# PX4FMUv2_4_6_10.net
KiCad netlist of a schematic drawn in Altium Designer
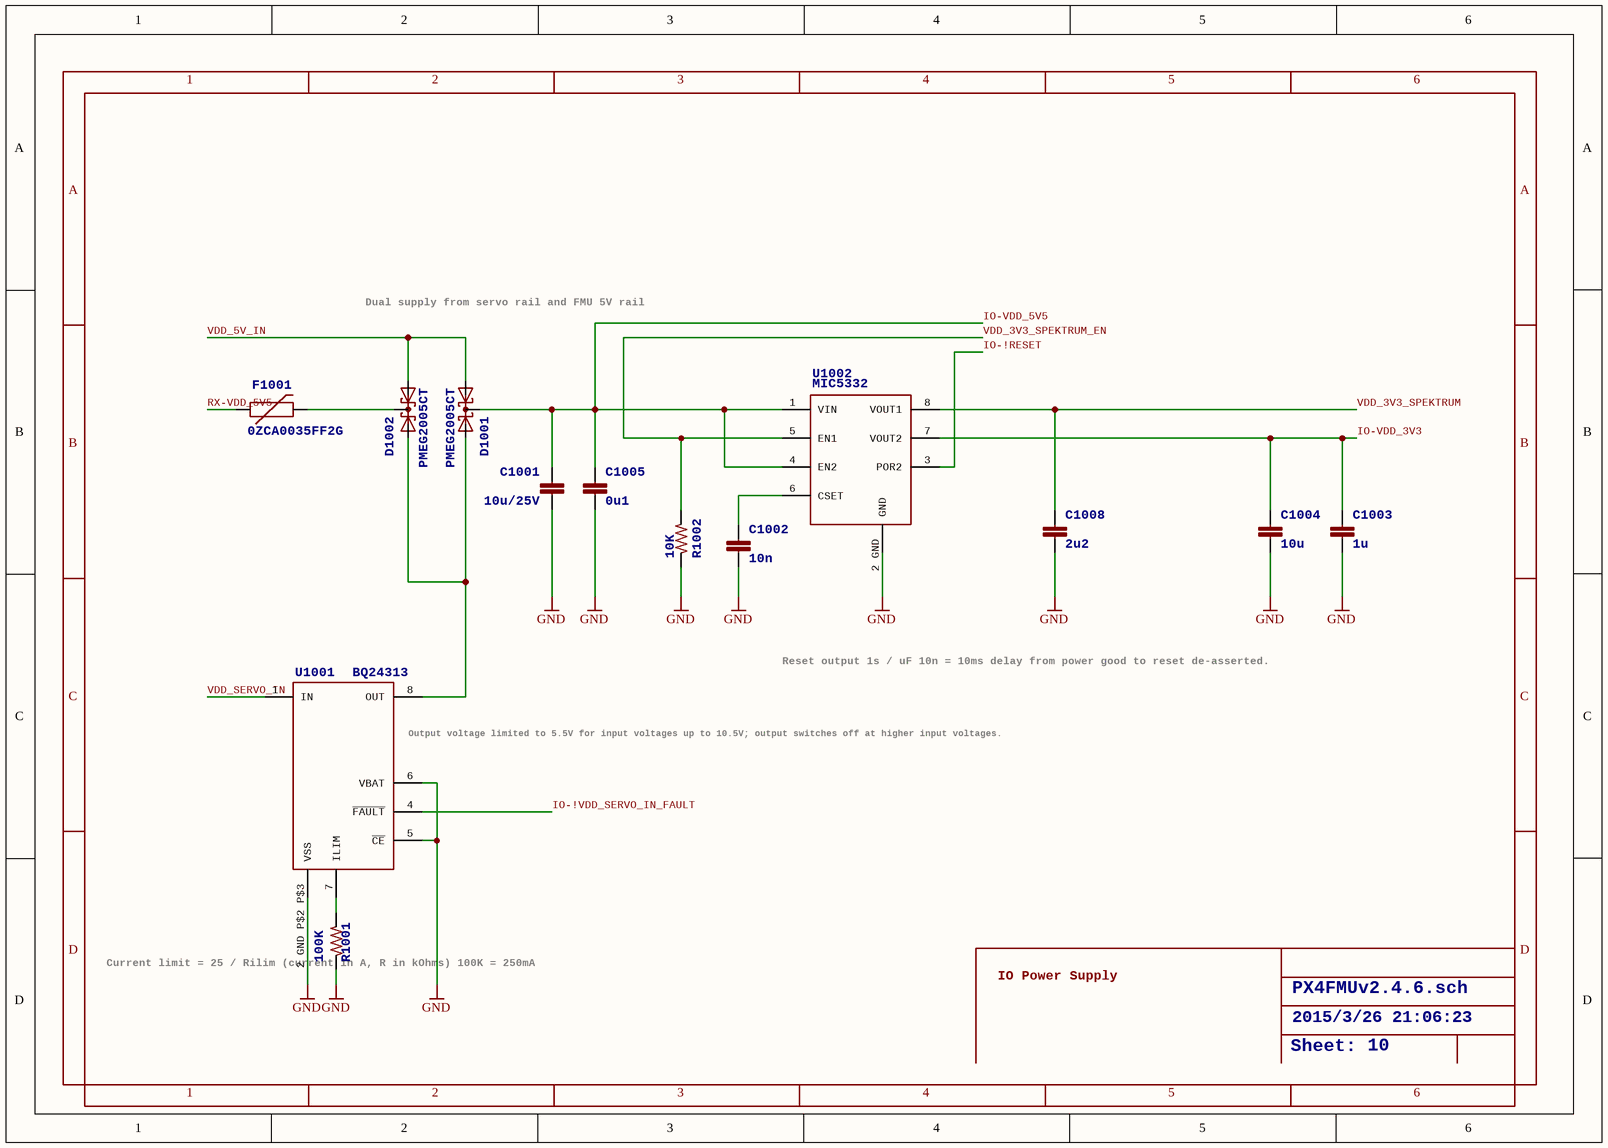
[diagram p0: PX4FMUv2.4.6_10.SchDoc]

(export (version "E")
  (design (tool "Eeschema 10.0.6"))
  (components
    (comp (ref "C1001")
      (value "10u/25V")
      (footprint "0805-CAP")
      (description "<b>Capacitor</b>\nStandard 0603 ceramic capacitor, and 0.1\" leaded capacitor.")
      (fields (field (name "PARTNO") "CL21A106KAYNNNE"))
      (libsource (lib "pixhawk2") (part "CAP0805"))
    )
    (comp (ref "C1002")
      (value "10n")
      (footprint "0402-CAP")
      (description "<b>Capacitor</b>\nStandard 0603 ceramic capacitor, and 0.1\" leaded capacitor.")
      (fields (field (name "PARTNO") "CC0402KRX7R7BB103"))
      (libsource (lib "pixhawk2") (part "CAP0402"))
    )
    (comp (ref "C1003")
      (value "1u")
      (footprint "0603-CAP")
      (description "<b>Capacitor</b>\nStandard 0603 ceramic capacitor, and 0.1\" leaded capacitor.")
      (fields (field (name "PARTNO") "CC0603ZRY5V7BB105"))
      (libsource (lib "pixhawk2") (part "CAP0603"))
    )
    (comp (ref "C1004")
      (value "10u")
      (footprint "0603-CAP")
      (description "<b>Capacitor</b>\nStandard 0603 ceramic capacitor, and 0.1\" leaded capacitor.")
      (fields (field (name "PARTNO") "C1608X5R1A106K080AC"))
      (libsource (lib "pixhawk2") (part "CAP0603"))
    )
    (comp (ref "C1005")
      (value "0u1")
      (footprint "0402-CAP")
      (description "<b>Capacitor</b>\nStandard 0603 ceramic capacitor, and 0.1\" leaded capacitor.")
      (fields (field (name "PARTNO") "CC0402ZRY5V7BB104"))
      (libsource (lib "pixhawk2") (part "CAP0402"))
    )
    (comp (ref "C1008")
      (value "2u2")
      (footprint "0402-CAP")
      (description "<b>Capacitor</b>\nStandard 0603 ceramic capacitor, and 0.1\" leaded capacitor.")
      (fields (field (name "PARTNO") "C1005X6S1C225K050BC"))
      (libsource (lib "pixhawk2") (part "CAP0402"))
    )
    (comp (ref "D1001")
      (value "PMEG2005CT")
      (footprint "SOT23-3")
      (libsource (lib "pixhawk2") (part "PMEG2005CT"))
    )
    (comp (ref "D1002")
      (value "PMEG2005CT")
      (footprint "SOT23-3")
      (libsource (lib "pixhawk2") (part "PMEG2005CT"))
    )
    (comp (ref "F1001")
      (value "0ZCA0035FF2G")
      (footprint "PTC-1206")
      (description "<b>Resettable Fuse PTC</b>\nResettable Fuse. Spark Fun Electronics SKU : COM-08357")
      (libsource (lib "pixhawk2") (part "PTCSMD"))
    )
    (comp (ref "R1001")
      (value "100K")
      (footprint "0402-RES")
      (libsource (lib "pixhawk2") (part "RESISTOR0402-RES"))
    )
    (comp (ref "R1002")
      (value "10K")
      (footprint "0402-RES")
      (fields (field (name "PARTNO") "RC0402FR-0710KL"))
      (libsource (lib "pixhawk2") (part "RESISTOR0402-RES"))
    )
    (comp (ref "U1001")
      (value "BQ24313")
      (footprint "QFN8-DSG")
      (fields (field (name "PARTNO") "BQ24313DSGT"))
      (libsource (lib "pixhawk2") (part "BQ24313"))
    )
    (comp (ref "U1002")
      (value "MIC5332")
      (footprint "MLF-8-EPAD")
      (fields (field (name "PARTNO") "MIC5332-SSYMT"))
      (libsource (lib "pixhawk2") (part "MIC5332"))
    )
  )
  (nets
    (net (code "1") (name "/IO-!RESET") (class "Default")
      (node (ref "U1002") (pin "3") (pinfunction "POR2_3") (pintype "passive"))
    )
    (net (code "2") (name "/IO-!VDD_SERVO_IN_FAULT") (class "Default")
      (node (ref "U1001") (pin "4") (pinfunction "~{FAULT}_4") (pintype "passive"))
    )
    (net (code "3") (name "/IO-VDD_3V3") (class "Default")
      (node (ref "C1003") (pin "P$1") (pinfunction "1_P$1") (pintype "passive"))
      (node (ref "C1004") (pin "P$1") (pinfunction "1_P$1") (pintype "passive"))
      (node (ref "U1002") (pin "7") (pinfunction "VOUT2_7") (pintype "passive"))
    )
    (net (code "4") (name "/IO-VDD_5V5") (class "Default")
      (node (ref "C1001") (pin "P$1") (pinfunction "1_P$1") (pintype "passive"))
      (node (ref "C1005") (pin "P$1") (pinfunction "1_P$1") (pintype "passive"))
      (node (ref "D1001") (pin "3") (pinfunction "CC_3") (pintype "passive"))
      (node (ref "U1002") (pin "1") (pinfunction "VIN_1") (pintype "passive"))
      (node (ref "U1002") (pin "4") (pinfunction "EN2_4") (pintype "passive"))
    )
    (net (code "5") (name "/RX-VDD_5V5") (class "Default")
      (node (ref "F1001") (pin "1") (pinfunction "1_1") (pintype "passive"))
    )
    (net (code "6") (name "/VDD_3V3_SPEKTRUM") (class "Default")
      (node (ref "C1008") (pin "P$1") (pinfunction "1_P$1") (pintype "passive"))
      (node (ref "U1002") (pin "8") (pinfunction "VOUT1_8") (pintype "passive"))
    )
    (net (code "7") (name "/VDD_3V3_SPEKTRUM_EN") (class "Default")
      (node (ref "R1002") (pin "P$2") (pinfunction "2_P$2") (pintype "passive"))
      (node (ref "U1002") (pin "5") (pinfunction "EN1_5") (pintype "passive"))
    )
    (net (code "8") (name "/VDD_5V_IN") (class "Default")
      (node (ref "D1001") (pin "1") (pinfunction "A1_1") (pintype "passive"))
      (node (ref "D1002") (pin "1") (pinfunction "A1_1") (pintype "passive"))
    )
    (net (code "9") (name "/VDD_SERVO_IN") (class "Default")
      (node (ref "U1001") (pin "1") (pinfunction "IN_1") (pintype "passive"))
    )
    (net (code "10") (name "GND") (class "Default")
      (node (ref "C1001") (pin "P$2") (pinfunction "2_P$2") (pintype "passive"))
      (node (ref "C1002") (pin "P$2") (pinfunction "2_P$2") (pintype "passive"))
      (node (ref "C1003") (pin "P$2") (pinfunction "2_P$2") (pintype "passive"))
      (node (ref "C1004") (pin "P$2") (pinfunction "2_P$2") (pintype "passive"))
      (node (ref "C1005") (pin "P$2") (pinfunction "2_P$2") (pintype "passive"))
      (node (ref "C1008") (pin "P$2") (pinfunction "2_P$2") (pintype "passive"))
      (node (ref "R1001") (pin "P$1") (pinfunction "1_P$1") (pintype "passive"))
      (node (ref "R1002") (pin "P$1") (pinfunction "1_P$1") (pintype "passive"))
      (node (ref "U1001") (pin "2_GND_P$2_P$3") (pinfunction "VSS_2_GND_P$2_P$3") (pintype "passive"))
      (node (ref "U1001") (pin "5") (pinfunction "~{CE}_5") (pintype "passive"))
      (node (ref "U1001") (pin "6") (pinfunction "VBAT_6") (pintype "passive"))
      (node (ref "U1002") (pin "2_GND") (pinfunction "GND_2_GND") (pintype "passive"))
    )
    (net (code "11") (name "Net-(C1002-1)") (class "Default")
      (node (ref "C1002") (pin "P$1") (pinfunction "1_P$1") (pintype "passive"))
      (node (ref "U1002") (pin "6") (pinfunction "CSET_6") (pintype "passive"))
    )
    (net (code "12") (name "Net-(D1001-A2)") (class "Default")
      (node (ref "D1001") (pin "2") (pinfunction "A2_2") (pintype "passive"))
      (node (ref "D1002") (pin "2") (pinfunction "A2_2") (pintype "passive"))
      (node (ref "U1001") (pin "8") (pinfunction "OUT_8") (pintype "passive"))
    )
    (net (code "13") (name "Net-(D1002-CC)") (class "Default")
      (node (ref "D1002") (pin "3") (pinfunction "CC_3") (pintype "passive"))
      (node (ref "F1001") (pin "2") (pinfunction "2_2") (pintype "passive"))
    )
    (net (code "14") (name "Net-(R1001-2)") (class "Default")
      (node (ref "R1001") (pin "P$2") (pinfunction "2_P$2") (pintype "passive"))
      (node (ref "U1001") (pin "7") (pinfunction "ILIM_7") (pintype "passive"))
    )
  )
)
